# oneKey_REV1.net
KiCad netlist of a schematic drawn in EAGLE
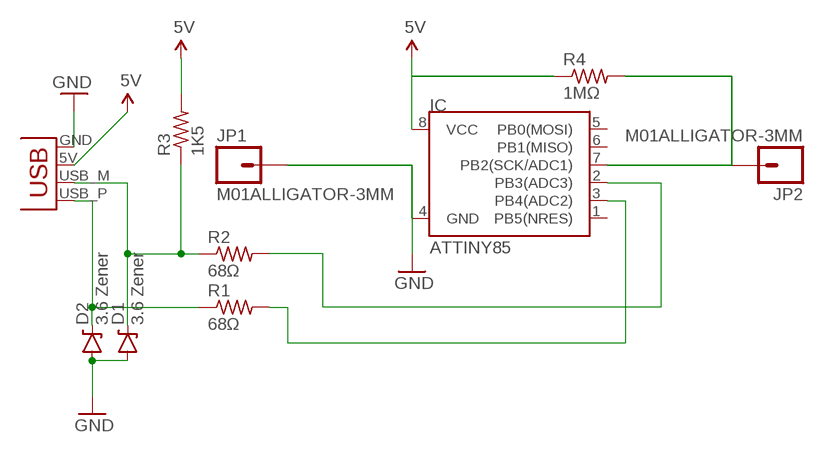
[diagram p0: schematic, sheet 1]

(export (version "E")
  (design (tool "Eeschema 10.0.6"))
  (components
    (comp (ref "D1")
      (value "3.6 Zener")
      (footprint "eagle-import:DIODE-ZENER")
      (libsource (lib "eagle-import") (part "DIODE-ZENERPTH"))
    )
    (comp (ref "D2")
      (value "3.6 Zener")
      (footprint "eagle-import:DIODE-ZENER")
      (libsource (lib "eagle-import") (part "DIODE-ZENERPTH"))
    )
    (comp (ref "IC")
      (value "ATTINY85")
      (footprint "eagle-import:DIP08")
      (libsource (lib "eagle-import") (part "ATTINY45DIP8"))
    )
    (comp (ref "JP1")
      (value "M01ALLIGATOR-3MM")
      (footprint "eagle-import:1X01_ALLIGATOR_3MM")
      (libsource (lib "eagle-import") (part "M01ALLIGATOR-3MM"))
    )
    (comp (ref "JP2")
      (value "M01ALLIGATOR-3MM")
      (footprint "eagle-import:1X01_ALLIGATOR_3MM")
      (libsource (lib "eagle-import") (part "M01ALLIGATOR-3MM"))
    )
    (comp (ref "R1")
      (value "68Ω")
      (footprint "eagle-import:0204_7")
      (libsource (lib "eagle-import") (part "R-US_0204/7"))
    )
    (comp (ref "R2")
      (value "68Ω")
      (footprint "eagle-import:0204_7")
      (libsource (lib "eagle-import") (part "R-US_0204/7"))
    )
    (comp (ref "R3")
      (value "1K5")
      (footprint "eagle-import:0204_7")
      (libsource (lib "eagle-import") (part "R-US_0204/7"))
    )
    (comp (ref "R4")
      (value "1MΩ")
      (footprint "eagle-import:0204_7")
      (libsource (lib "eagle-import") (part "R-US_0204/7"))
    )
    (comp (ref "X1")
      (value "USBPCB")
      (footprint "eagle-import:USB-A-PCB")
      (libsource (lib "eagle-import") (part "USBPCB"))
    )
  )
  (nets
    (net (code "1") (name "5V") (class "Default")
      (node (ref "IC") (pin "8") (pinfunction "VCC_8") (pintype "bidirectional"))
      (node (ref "R3") (pin "2") (pinfunction "2_2") (pintype "passive"))
      (node (ref "R4") (pin "1") (pinfunction "1_1") (pintype "passive"))
      (node (ref "X1") (pin "5V") (pinfunction "VBUS_5V") (pintype "bidirectional"))
    )
    (net (code "2") (name "GND") (class "Default")
      (node (ref "D1") (pin "P$2") (pinfunction "A_P$2") (pintype "passive"))
      (node (ref "D2") (pin "P$2") (pinfunction "A_P$2") (pintype "passive"))
      (node (ref "IC") (pin "4") (pinfunction "GND_4") (pintype "bidirectional"))
      (node (ref "JP1") (pin "1@0") (pinfunction "1_1@0") (pintype "passive"))
      (node (ref "JP1") (pin "1@2") (pinfunction "1_1@2") (pintype "passive"))
      (node (ref "X1") (pin "GND") (pinfunction "GND_GND") (pintype "bidirectional"))
    )
    (net (code "3") (name "Net-(D1-C)") (class "Default")
      (node (ref "D1") (pin "P$1") (pinfunction "C_P$1") (pintype "passive"))
      (node (ref "R2") (pin "1") (pinfunction "1_1") (pintype "passive"))
      (node (ref "R3") (pin "1") (pinfunction "1_1") (pintype "passive"))
      (node (ref "X1") (pin "USB_M") (pinfunction "D-_USB_M") (pintype "bidirectional"))
    )
    (net (code "4") (name "Net-(D2-C)") (class "Default")
      (node (ref "D2") (pin "P$1") (pinfunction "C_P$1") (pintype "passive"))
      (node (ref "R1") (pin "1") (pinfunction "1_1") (pintype "passive"))
      (node (ref "X1") (pin "USB_P") (pinfunction "D+_USB_P") (pintype "bidirectional"))
    )
    (net (code "5") (name "Net-(IC-PB2(SCK{slash}ADC1))") (class "Default")
      (node (ref "IC") (pin "7") (pinfunction "PB2(SCK/ADC1)_7") (pintype "bidirectional"))
      (node (ref "JP2") (pin "1@0") (pinfunction "1_1@0") (pintype "passive"))
      (node (ref "JP2") (pin "1@2") (pinfunction "1_1@2") (pintype "passive"))
      (node (ref "R4") (pin "2") (pinfunction "2_2") (pintype "passive"))
    )
    (net (code "6") (name "Net-(IC-PB3(ADC3))") (class "Default")
      (node (ref "IC") (pin "2") (pinfunction "PB3(ADC3)_2") (pintype "bidirectional"))
      (node (ref "R2") (pin "2") (pinfunction "2_2") (pintype "passive"))
    )
    (net (code "7") (name "Net-(IC-PB4(ADC2))") (class "Default")
      (node (ref "IC") (pin "3") (pinfunction "PB4(ADC2)_3") (pintype "bidirectional"))
      (node (ref "R1") (pin "2") (pinfunction "2_2") (pintype "passive"))
    )
    (net (code "8") (name "unconnected-(IC-PB0(MOSI)-Pad5)") (class "Default")
      (node (ref "IC") (pin "5") (pinfunction "PB0(MOSI)_5") (pintype "bidirectional"))
    )
    (net (code "9") (name "unconnected-(IC-PB1(MISO)-Pad6)") (class "Default")
      (node (ref "IC") (pin "6") (pinfunction "PB1(MISO)_6") (pintype "bidirectional"))
    )
    (net (code "10") (name "unconnected-(IC-PB5(NRES)-Pad1)") (class "Default")
      (node (ref "IC") (pin "1") (pinfunction "PB5(NRES)_1") (pintype "bidirectional"))
    )
  )
)
